# XMICRO-BREAKOUT-BREADBOARD.net
KiCad netlist of a schematic drawn in EAGLE
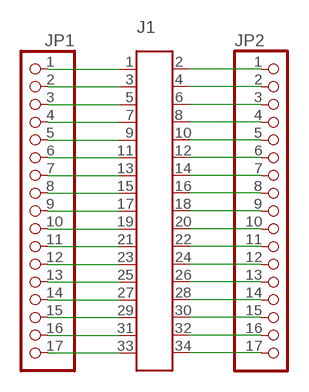
[diagram p0: schematic, sheet 1]

(export (version "E")
  (design (tool "Eeschema 10.0.6"))
  (components
    (comp (ref "J1")
      (value "HDR-17X2")
      (footprint "eagle-import:HDR-17X2S")
      (libsource (lib "eagle-import") (part "HDR-17X2"))
    )
    (comp (ref "JP1")
      (value "PINHD-1X17")
      (footprint "eagle-import:1X17")
      (libsource (lib "eagle-import") (part "PINHD-1X17"))
    )
    (comp (ref "JP2")
      (value "PINHD-1X17")
      (footprint "eagle-import:1X17")
      (libsource (lib "eagle-import") (part "PINHD-1X17"))
    )
  )
  (nets
    (net (code "1") (name "Net-(J1-Pad1)") (class "Default")
      (node (ref "J1") (pin "1") (pinfunction "1_1") (pintype "bidirectional"))
      (node (ref "JP1") (pin "1") (pinfunction "1_1") (pintype "passive"))
    )
    (net (code "2") (name "Net-(J1-Pad2)") (class "Default")
      (node (ref "J1") (pin "2") (pinfunction "2_2") (pintype "bidirectional"))
      (node (ref "JP2") (pin "1") (pinfunction "1_1") (pintype "passive"))
    )
    (net (code "3") (name "Net-(J1-Pad3)") (class "Default")
      (node (ref "J1") (pin "3") (pinfunction "3_3") (pintype "bidirectional"))
      (node (ref "JP1") (pin "2") (pinfunction "2_2") (pintype "passive"))
    )
    (net (code "4") (name "Net-(J1-Pad4)") (class "Default")
      (node (ref "J1") (pin "4") (pinfunction "4_4") (pintype "bidirectional"))
      (node (ref "JP2") (pin "2") (pinfunction "2_2") (pintype "passive"))
    )
    (net (code "5") (name "Net-(J1-Pad5)") (class "Default")
      (node (ref "J1") (pin "5") (pinfunction "5_5") (pintype "bidirectional"))
      (node (ref "JP1") (pin "3") (pinfunction "3_3") (pintype "passive"))
    )
    (net (code "6") (name "Net-(J1-Pad6)") (class "Default")
      (node (ref "J1") (pin "6") (pinfunction "6_6") (pintype "bidirectional"))
      (node (ref "JP2") (pin "3") (pinfunction "3_3") (pintype "passive"))
    )
    (net (code "7") (name "Net-(J1-Pad7)") (class "Default")
      (node (ref "J1") (pin "7") (pinfunction "7_7") (pintype "bidirectional"))
      (node (ref "JP1") (pin "4") (pinfunction "4_4") (pintype "passive"))
    )
    (net (code "8") (name "Net-(J1-Pad8)") (class "Default")
      (node (ref "J1") (pin "8") (pinfunction "8_8") (pintype "bidirectional"))
      (node (ref "JP2") (pin "4") (pinfunction "4_4") (pintype "passive"))
    )
    (net (code "9") (name "Net-(J1-Pad9)") (class "Default")
      (node (ref "J1") (pin "9") (pinfunction "9_9") (pintype "bidirectional"))
      (node (ref "JP1") (pin "5") (pinfunction "5_5") (pintype "passive"))
    )
    (net (code "10") (name "Net-(J1-Pad10)") (class "Default")
      (node (ref "J1") (pin "10") (pinfunction "10_10") (pintype "bidirectional"))
      (node (ref "JP2") (pin "5") (pinfunction "5_5") (pintype "passive"))
    )
    (net (code "11") (name "Net-(J1-Pad11)") (class "Default")
      (node (ref "J1") (pin "11") (pinfunction "11_11") (pintype "bidirectional"))
      (node (ref "JP1") (pin "6") (pinfunction "6_6") (pintype "passive"))
    )
    (net (code "12") (name "Net-(J1-Pad12)") (class "Default")
      (node (ref "J1") (pin "12") (pinfunction "12_12") (pintype "bidirectional"))
      (node (ref "JP2") (pin "6") (pinfunction "6_6") (pintype "passive"))
    )
    (net (code "13") (name "Net-(J1-Pad13)") (class "Default")
      (node (ref "J1") (pin "13") (pinfunction "13_13") (pintype "bidirectional"))
      (node (ref "JP1") (pin "7") (pinfunction "7_7") (pintype "passive"))
    )
    (net (code "14") (name "Net-(J1-Pad14)") (class "Default")
      (node (ref "J1") (pin "14") (pinfunction "14_14") (pintype "bidirectional"))
      (node (ref "JP2") (pin "7") (pinfunction "7_7") (pintype "passive"))
    )
    (net (code "15") (name "Net-(J1-Pad15)") (class "Default")
      (node (ref "J1") (pin "15") (pinfunction "15_15") (pintype "bidirectional"))
      (node (ref "JP1") (pin "8") (pinfunction "8_8") (pintype "passive"))
    )
    (net (code "16") (name "Net-(J1-Pad16)") (class "Default")
      (node (ref "J1") (pin "16") (pinfunction "16_16") (pintype "bidirectional"))
      (node (ref "JP2") (pin "8") (pinfunction "8_8") (pintype "passive"))
    )
    (net (code "17") (name "Net-(J1-Pad17)") (class "Default")
      (node (ref "J1") (pin "17") (pinfunction "17_17") (pintype "bidirectional"))
      (node (ref "JP1") (pin "9") (pinfunction "9_9") (pintype "passive"))
    )
    (net (code "18") (name "Net-(J1-Pad18)") (class "Default")
      (node (ref "J1") (pin "18") (pinfunction "18_18") (pintype "bidirectional"))
      (node (ref "JP2") (pin "9") (pinfunction "9_9") (pintype "passive"))
    )
    (net (code "19") (name "Net-(J1-Pad19)") (class "Default")
      (node (ref "J1") (pin "19") (pinfunction "19_19") (pintype "bidirectional"))
      (node (ref "JP1") (pin "10") (pinfunction "10_10") (pintype "passive"))
    )
    (net (code "20") (name "Net-(J1-Pad20)") (class "Default")
      (node (ref "J1") (pin "20") (pinfunction "20_20") (pintype "bidirectional"))
      (node (ref "JP2") (pin "10") (pinfunction "10_10") (pintype "passive"))
    )
    (net (code "21") (name "Net-(J1-Pad21)") (class "Default")
      (node (ref "J1") (pin "21") (pinfunction "21_21") (pintype "bidirectional"))
      (node (ref "JP1") (pin "11") (pinfunction "11_11") (pintype "passive"))
    )
    (net (code "22") (name "Net-(J1-Pad22)") (class "Default")
      (node (ref "J1") (pin "22") (pinfunction "22_22") (pintype "bidirectional"))
      (node (ref "JP2") (pin "11") (pinfunction "11_11") (pintype "passive"))
    )
    (net (code "23") (name "Net-(J1-Pad23)") (class "Default")
      (node (ref "J1") (pin "23") (pinfunction "23_23") (pintype "bidirectional"))
      (node (ref "JP1") (pin "12") (pinfunction "12_12") (pintype "passive"))
    )
    (net (code "24") (name "Net-(J1-Pad24)") (class "Default")
      (node (ref "J1") (pin "24") (pinfunction "24_24") (pintype "bidirectional"))
      (node (ref "JP2") (pin "12") (pinfunction "12_12") (pintype "passive"))
    )
    (net (code "25") (name "Net-(J1-Pad25)") (class "Default")
      (node (ref "J1") (pin "25") (pinfunction "25_25") (pintype "bidirectional"))
      (node (ref "JP1") (pin "13") (pinfunction "13_13") (pintype "passive"))
    )
    (net (code "26") (name "Net-(J1-Pad26)") (class "Default")
      (node (ref "J1") (pin "26") (pinfunction "26_26") (pintype "bidirectional"))
      (node (ref "JP2") (pin "13") (pinfunction "13_13") (pintype "passive"))
    )
    (net (code "27") (name "Net-(J1-Pad27)") (class "Default")
      (node (ref "J1") (pin "27") (pinfunction "27_27") (pintype "bidirectional"))
      (node (ref "JP1") (pin "14") (pinfunction "14_14") (pintype "passive"))
    )
    (net (code "28") (name "Net-(J1-Pad28)") (class "Default")
      (node (ref "J1") (pin "28") (pinfunction "28_28") (pintype "bidirectional"))
      (node (ref "JP2") (pin "14") (pinfunction "14_14") (pintype "passive"))
    )
    (net (code "29") (name "Net-(J1-Pad29)") (class "Default")
      (node (ref "J1") (pin "29") (pinfunction "29_29") (pintype "bidirectional"))
      (node (ref "JP1") (pin "15") (pinfunction "15_15") (pintype "passive"))
    )
    (net (code "30") (name "Net-(J1-Pad30)") (class "Default")
      (node (ref "J1") (pin "30") (pinfunction "30_30") (pintype "bidirectional"))
      (node (ref "JP2") (pin "15") (pinfunction "15_15") (pintype "passive"))
    )
    (net (code "31") (name "Net-(J1-Pad31)") (class "Default")
      (node (ref "J1") (pin "31") (pinfunction "31_31") (pintype "bidirectional"))
      (node (ref "JP1") (pin "16") (pinfunction "16_16") (pintype "passive"))
    )
    (net (code "32") (name "Net-(J1-Pad32)") (class "Default")
      (node (ref "J1") (pin "32") (pinfunction "32_32") (pintype "bidirectional"))
      (node (ref "JP2") (pin "16") (pinfunction "16_16") (pintype "passive"))
    )
    (net (code "33") (name "Net-(J1-Pad33)") (class "Default")
      (node (ref "J1") (pin "33") (pinfunction "33_33") (pintype "bidirectional"))
      (node (ref "JP1") (pin "17") (pinfunction "17_17") (pintype "passive"))
    )
    (net (code "34") (name "Net-(J1-Pad34)") (class "Default")
      (node (ref "J1") (pin "34") (pinfunction "34_34") (pintype "bidirectional"))
      (node (ref "JP2") (pin "17") (pinfunction "17_17") (pintype "passive"))
    )
  )
)
